# Cansat2019_1516_Payload_SectionA_v01.net
KiCad netlist of a schematic drawn in EAGLE
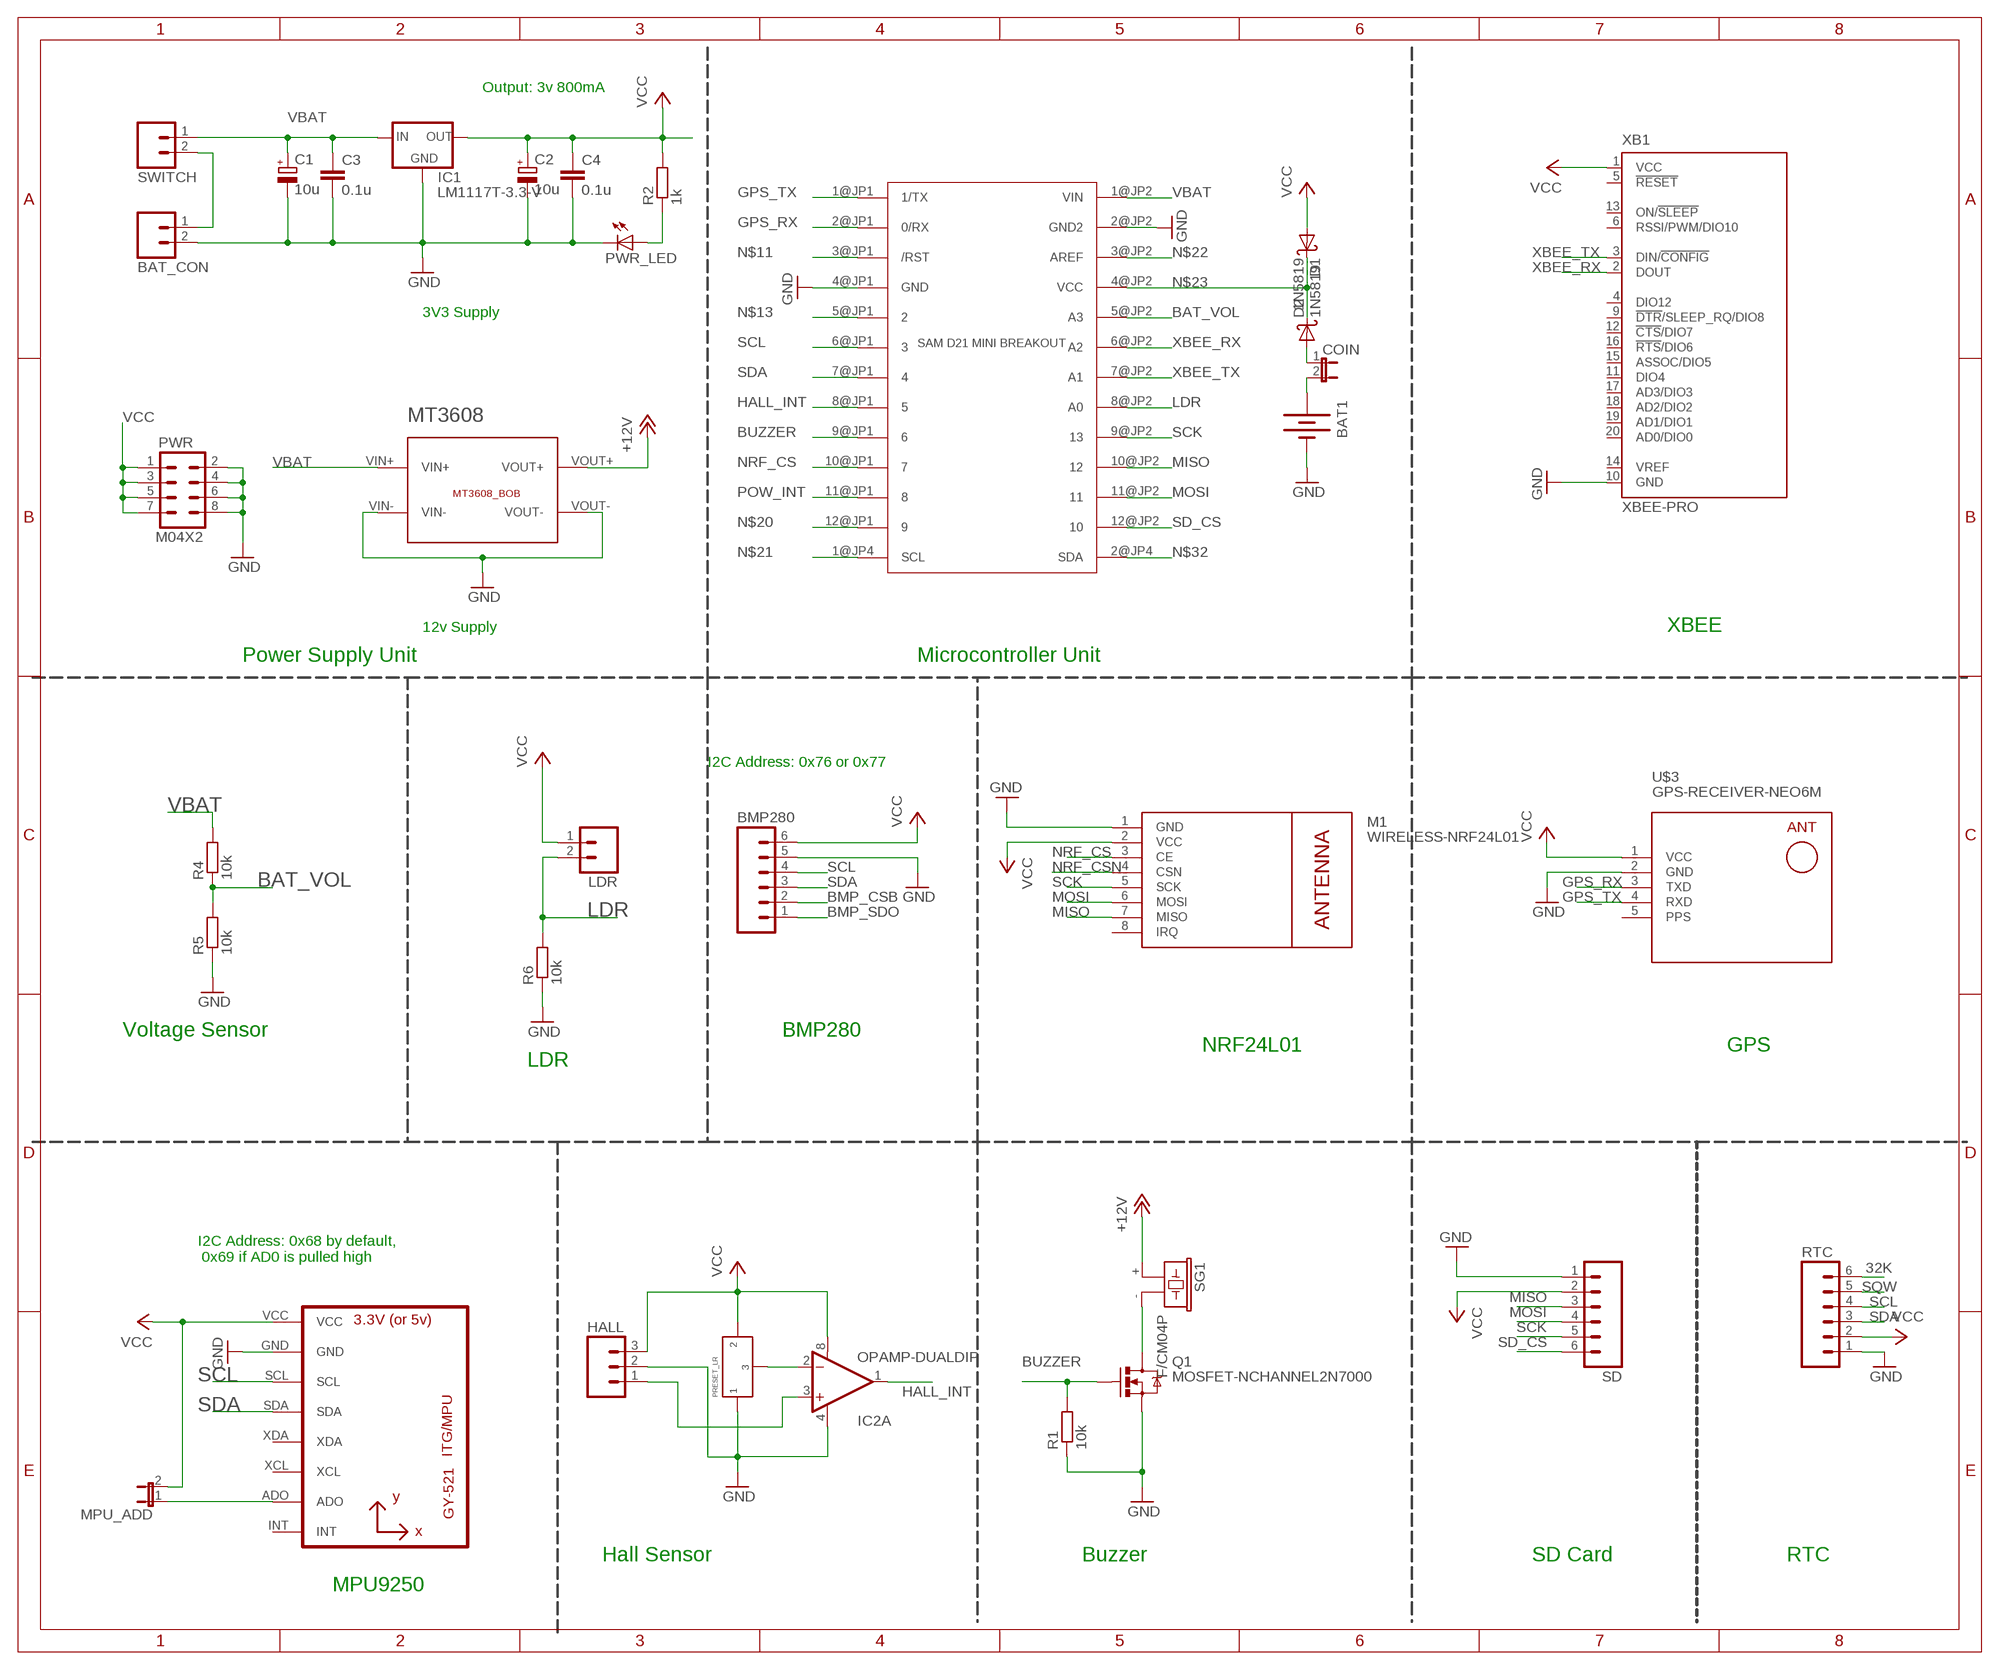
[diagram p0: schematic, sheet 1]

(export (version "E")
  (design (tool "Eeschema 10.0.6"))
  (components
    (comp (ref "BAT1")
      (value "BATTERY20PTH")
      (footprint "eagle-import:BATTCOM_20MM_PTH")
      (libsource (lib "eagle-import") (part "BATTERY20PTH"))
    )
    (comp (ref "BAT_CON")
      (value "M02")
      (footprint "eagle-import:02P")
      (libsource (lib "eagle-import") (part "M02"))
    )
    (comp (ref "BMP280")
      (value "M06")
      (footprint "eagle-import:06P")
      (libsource (lib "eagle-import") (part "M06"))
    )
    (comp (ref "C1")
      (value "10u")
      (footprint "eagle-import:E2,5-6")
      (libsource (lib "eagle-import") (part "CPOL-EUE2.5-6"))
    )
    (comp (ref "C2")
      (value "10u")
      (footprint "eagle-import:E2,5-6")
      (libsource (lib "eagle-import") (part "CPOL-EUE2.5-6"))
    )
    (comp (ref "C3")
      (value "0.1u")
      (footprint "eagle-import:C025-025X050")
      (libsource (lib "eagle-import") (part "C-EU025-025X050"))
    )
    (comp (ref "C4")
      (value "0.1u")
      (footprint "eagle-import:C025-025X050")
      (libsource (lib "eagle-import") (part "C-EU025-025X050"))
    )
    (comp (ref "COIN")
      (value "JUMPER-2PTH")
      (footprint "eagle-import:1X02")
      (libsource (lib "eagle-import") (part "JUMPER-2PTH"))
    )
    (comp (ref "D1")
      (value "1N5819")
      (footprint "eagle-import:DO41-10")
      (libsource (lib "eagle-import") (part "1N5819"))
    )
    (comp (ref "D2")
      (value "1N5819")
      (footprint "eagle-import:DO41-10")
      (libsource (lib "eagle-import") (part "1N5819"))
    )
    (comp (ref "HALL")
      (value "M03")
      (footprint "eagle-import:03P")
      (libsource (lib "eagle-import") (part "M03"))
    )
    (comp (ref "IC1")
      (value "LM1117T-3.3-V")
      (footprint "eagle-import:TO220V")
      (libsource (lib "eagle-import") (part "LM1117T--V3.3"))
    )
    (comp (ref "IC2")
      (value "OPAMP-DUALDIP")
      (footprint "eagle-import:DIP08")
      (libsource (lib "eagle-import") (part "OPAMP-DUALDIP"))
    )
    (comp (ref "LDR")
      (value "M02")
      (footprint "eagle-import:02P")
      (libsource (lib "eagle-import") (part "M02"))
    )
    (comp (ref "M1")
      (value "WIRELESS-NRF24L01")
      (footprint "eagle-import:WIRELESS-NRF24L01")
      (libsource (lib "eagle-import") (part "WIRELESS-NRF24L01"))
    )
    (comp (ref "MPU_ADD")
      (value "JUMPER-2PTH")
      (footprint "eagle-import:1X02")
      (libsource (lib "eagle-import") (part "JUMPER-2PTH"))
    )
    (comp (ref "MT3608")
      (value "MT3608_BOB")
      (footprint "eagle-import:MT3608_BOB")
      (libsource (lib "eagle-import") (part "MT3608_BOB"))
    )
    (comp (ref "PWR")
      (value "M04X2")
      (footprint "eagle-import:2X4")
      (libsource (lib "eagle-import") (part "M04X2"))
    )
    (comp (ref "PWR_LED")
      (value "LED3MM")
      (footprint "eagle-import:LED3MM")
      (libsource (lib "eagle-import") (part "LED3MM"))
    )
    (comp (ref "Q1")
      (value "MOSFET-NCHANNEL2N7000")
      (footprint "eagle-import:TO-92")
      (libsource (lib "eagle-import") (part "MOSFET-NCHANNEL2N7000"))
    )
    (comp (ref "R1")
      (value "10k")
      (footprint "eagle-import:0204_7")
      (libsource (lib "eagle-import") (part "R-EU_0204/7"))
    )
    (comp (ref "R2")
      (value "1k")
      (footprint "eagle-import:0204_7")
      (libsource (lib "eagle-import") (part "R-EU_0204/7"))
    )
    (comp (ref "R4")
      (value "10k")
      (footprint "eagle-import:0204_7")
      (libsource (lib "eagle-import") (part "R-EU_0204/7"))
    )
    (comp (ref "R5")
      (value "10k")
      (footprint "eagle-import:0204_7")
      (libsource (lib "eagle-import") (part "R-EU_0204/7"))
    )
    (comp (ref "R6")
      (value "10k")
      (footprint "eagle-import:0204_7")
      (libsource (lib "eagle-import") (part "R-EU_0204/7"))
    )
    (comp (ref "RTC")
      (value "M06")
      (footprint "eagle-import:06P")
      (libsource (lib "eagle-import") (part "M06"))
    )
    (comp (ref "SD")
      (value "M06")
      (footprint "eagle-import:06P")
      (libsource (lib "eagle-import") (part "M06"))
    )
    (comp (ref "SG1")
      (value "F/CM04P")
      (footprint "eagle-import:F_CM04P")
      (libsource (lib "eagle-import") (part "F/CM04P"))
    )
    (comp (ref "SWITCH")
      (value "M02")
      (footprint "eagle-import:02P")
      (libsource (lib "eagle-import") (part "M02"))
    )
    (comp (ref "U$1")
      (value "SAM_D21_MINI_BREAKOUT")
      (footprint "eagle-import:JP1_SPARKFUN-SAMD21-MINI-BREAKOUT-V10")
      (libsource (lib "eagle-import") (part "SAM_D21_MINI_BREAKOUT"))
    )
    (comp (ref "U$2")
      (value "PRESET_LR")
      (footprint "eagle-import:PRESET_LR")
      (libsource (lib "eagle-import") (part "PRESET_LR"))
    )
    (comp (ref "U$3")
      (value "GPS-RECEIVER-NEO6M")
      (footprint "eagle-import:GPS-RECEIVER-NEO6M")
      (libsource (lib "eagle-import") (part "GPS-RECEIVER-NEO6M"))
    )
    (comp (ref "U1")
      (value "GY-521MPU6050")
      (footprint "eagle-import:GY-521")
      (libsource (lib "eagle-import") (part "GY-521MPU6050"))
    )
    (comp (ref "XB1")
      (value "XBEE-PRO")
      (footprint "eagle-import:XBEE-PRO")
      (fields (field (name "MPN") "XBP24-AWI-001"))
      (libsource (lib "eagle-import") (part "XBEE-PRO"))
    )
  )
  (nets
    (net (code "1") (name "+12V") (class "Default")
      (node (ref "MT3608") (pin "VOUT+") (pinfunction "VOUT+_VOUT+") (pintype "bidirectional"))
      (node (ref "SG1") (pin "+") (pinfunction "1_+") (pintype "passive"))
    )
    (net (code "2") (name "/32K") (class "Default")
      (node (ref "RTC") (pin "6") (pinfunction "6_6") (pintype "passive"))
    )
    (net (code "3") (name "/BAT_VOL") (class "Default")
      (node (ref "R4") (pin "1") (pinfunction "1_1") (pintype "passive"))
      (node (ref "R5") (pin "2") (pinfunction "2_2") (pintype "passive"))
      (node (ref "U$1") (pin "5@JP2") (pinfunction "A3_5@JP2") (pintype "bidirectional"))
    )
    (net (code "4") (name "/BMP_CSB") (class "Default")
      (node (ref "BMP280") (pin "2") (pinfunction "2_2") (pintype "passive"))
    )
    (net (code "5") (name "/BMP_SDO") (class "Default")
      (node (ref "BMP280") (pin "1") (pinfunction "1_1") (pintype "passive"))
    )
    (net (code "6") (name "/BUZZER") (class "Default")
      (node (ref "Q1") (pin "2") (pinfunction "G_2") (pintype "passive"))
      (node (ref "R1") (pin "2") (pinfunction "2_2") (pintype "passive"))
      (node (ref "U$1") (pin "9@JP1") (pinfunction "6_9@JP1") (pintype "bidirectional"))
    )
    (net (code "7") (name "/GPS_RX") (class "Default")
      (node (ref "U$1") (pin "2@JP1") (pinfunction "0/RX_2@JP1") (pintype "bidirectional"))
      (node (ref "U$3") (pin "3") (pinfunction "TXD_3") (pintype "bidirectional"))
    )
    (net (code "8") (name "/GPS_TX") (class "Default")
      (node (ref "U$1") (pin "1@JP1") (pinfunction "1/TX_1@JP1") (pintype "bidirectional"))
      (node (ref "U$3") (pin "4") (pinfunction "RXD_4") (pintype "power_in"))
    )
    (net (code "9") (name "/HALL_INT") (class "Default")
      (node (ref "IC2") (pin "1") (pinfunction "OUT_1") (pintype "output"))
      (node (ref "U$1") (pin "8@JP1") (pinfunction "5_8@JP1") (pintype "bidirectional"))
    )
    (net (code "10") (name "/LDR") (class "Default")
      (node (ref "LDR") (pin "2") (pinfunction "2_2") (pintype "passive"))
      (node (ref "R6") (pin "2") (pinfunction "2_2") (pintype "passive"))
      (node (ref "U$1") (pin "8@JP2") (pinfunction "A0_8@JP2") (pintype "bidirectional"))
    )
    (net (code "11") (name "/MISO") (class "Default")
      (node (ref "M1") (pin "7") (pinfunction "MISO_7") (pintype "bidirectional"))
      (node (ref "SD") (pin "3") (pinfunction "3_3") (pintype "passive"))
      (node (ref "U$1") (pin "10@JP2") (pinfunction "12_10@JP2") (pintype "bidirectional"))
    )
    (net (code "12") (name "/MOSI") (class "Default")
      (node (ref "M1") (pin "6") (pinfunction "MOSI_6") (pintype "bidirectional"))
      (node (ref "SD") (pin "4") (pinfunction "4_4") (pintype "passive"))
      (node (ref "U$1") (pin "11@JP2") (pinfunction "11_11@JP2") (pintype "bidirectional"))
    )
    (net (code "13") (name "/N$11") (class "Default")
      (node (ref "U$1") (pin "3@JP1") (pinfunction "/RST_3@JP1") (pintype "input"))
    )
    (net (code "14") (name "/N$13") (class "Default")
      (node (ref "U$1") (pin "5@JP1") (pinfunction "2_5@JP1") (pintype "bidirectional"))
    )
    (net (code "15") (name "/N$20") (class "Default")
      (node (ref "U$1") (pin "12@JP1") (pinfunction "9_12@JP1") (pintype "bidirectional"))
    )
    (net (code "16") (name "/N$21") (class "Default")
      (node (ref "U$1") (pin "1@JP4") (pinfunction "SCL_1@JP4") (pintype "bidirectional"))
    )
    (net (code "17") (name "/N$22") (class "Default")
      (node (ref "U$1") (pin "3@JP2") (pinfunction "AREF_3@JP2") (pintype "power_in"))
    )
    (net (code "18") (name "/N$23") (class "Default")
      (node (ref "D1") (pin "C") (pinfunction "C_C") (pintype "passive"))
      (node (ref "D2") (pin "C") (pinfunction "C_C") (pintype "passive"))
      (node (ref "U$1") (pin "4@JP2") (pinfunction "VCC_4@JP2") (pintype "power_in"))
    )
    (net (code "19") (name "/N$32") (class "Default")
      (node (ref "U$1") (pin "2@JP4") (pinfunction "SDA_2@JP4") (pintype "bidirectional"))
    )
    (net (code "20") (name "/NRF_CS") (class "Default")
      (node (ref "M1") (pin "3") (pinfunction "CE_3") (pintype "bidirectional"))
      (node (ref "U$1") (pin "10@JP1") (pinfunction "7_10@JP1") (pintype "bidirectional"))
    )
    (net (code "21") (name "/NRF_CSN") (class "Default")
      (node (ref "M1") (pin "4") (pinfunction "CSN_4") (pintype "bidirectional"))
    )
    (net (code "22") (name "/POW_INT") (class "Default")
      (node (ref "U$1") (pin "11@JP1") (pinfunction "8_11@JP1") (pintype "bidirectional"))
    )
    (net (code "23") (name "/PPS") (class "Default")
      (node (ref "U$3") (pin "5") (pinfunction "PPS_5") (pintype "power_in"))
    )
    (net (code "24") (name "/SCK") (class "Default")
      (node (ref "M1") (pin "5") (pinfunction "SCK_5") (pintype "bidirectional"))
      (node (ref "SD") (pin "5") (pinfunction "5_5") (pintype "passive"))
      (node (ref "U$1") (pin "9@JP2") (pinfunction "13_9@JP2") (pintype "bidirectional"))
    )
    (net (code "25") (name "/SCL") (class "Default")
      (node (ref "BMP280") (pin "4") (pinfunction "4_4") (pintype "passive"))
      (node (ref "RTC") (pin "4") (pinfunction "4_4") (pintype "passive"))
      (node (ref "U$1") (pin "6@JP1") (pinfunction "3_6@JP1") (pintype "bidirectional"))
      (node (ref "U1") (pin "SCL") (pinfunction "SCL_SCL") (pintype "bidirectional"))
    )
    (net (code "26") (name "/SDA") (class "Default")
      (node (ref "BMP280") (pin "3") (pinfunction "3_3") (pintype "passive"))
      (node (ref "RTC") (pin "3") (pinfunction "3_3") (pintype "passive"))
      (node (ref "U$1") (pin "7@JP1") (pinfunction "4_7@JP1") (pintype "bidirectional"))
      (node (ref "U1") (pin "SDA") (pinfunction "SDA_SDA") (pintype "bidirectional"))
    )
    (net (code "27") (name "/SD_CS") (class "Default")
      (node (ref "SD") (pin "6") (pinfunction "6_6") (pintype "passive"))
      (node (ref "U$1") (pin "12@JP2") (pinfunction "10_12@JP2") (pintype "bidirectional"))
    )
    (net (code "28") (name "/SQW") (class "Default")
      (node (ref "RTC") (pin "5") (pinfunction "5_5") (pintype "passive"))
    )
    (net (code "29") (name "/VBAT") (class "Default")
      (node (ref "C1") (pin "+") (pinfunction "+_+") (pintype "passive"))
      (node (ref "C3") (pin "1") (pinfunction "1_1") (pintype "passive"))
      (node (ref "IC1") (pin "3") (pinfunction "IN_3") (pintype "input"))
      (node (ref "MT3608") (pin "VIN+") (pinfunction "VIN+_VIN+") (pintype "bidirectional"))
      (node (ref "R4") (pin "2") (pinfunction "2_2") (pintype "passive"))
      (node (ref "SWITCH") (pin "1") (pinfunction "1_1") (pintype "passive"))
      (node (ref "U$1") (pin "1@JP2") (pinfunction "VIN_1@JP2") (pintype "power_in"))
    )
    (net (code "30") (name "/XBEE_RX") (class "Default")
      (node (ref "U$1") (pin "6@JP2") (pinfunction "A2_6@JP2") (pintype "bidirectional"))
      (node (ref "XB1") (pin "2") (pinfunction "DOUT_2") (pintype "output"))
    )
    (net (code "31") (name "/XBEE_TX") (class "Default")
      (node (ref "U$1") (pin "7@JP2") (pinfunction "A1_7@JP2") (pintype "bidirectional"))
      (node (ref "XB1") (pin "3") (pinfunction "DIN/~{CONFIG}_3") (pintype "input"))
    )
    (net (code "32") (name "GND") (class "Default")
      (node (ref "BAT1") (pin "2") (pinfunction "-_2") (pintype "power_in"))
      (node (ref "BAT_CON") (pin "2") (pinfunction "2_2") (pintype "passive"))
      (node (ref "BMP280") (pin "5") (pinfunction "5_5") (pintype "passive"))
      (node (ref "C1") (pin "-") (pinfunction "-_-") (pintype "passive"))
      (node (ref "C2") (pin "-") (pinfunction "-_-") (pintype "passive"))
      (node (ref "C3") (pin "2") (pinfunction "2_2") (pintype "passive"))
      (node (ref "C4") (pin "2") (pinfunction "2_2") (pintype "passive"))
      (node (ref "HALL") (pin "2") (pinfunction "2_2") (pintype "passive"))
      (node (ref "IC1") (pin "1") (pinfunction "GND_1") (pintype "input"))
      (node (ref "IC2") (pin "4") (pinfunction "V-_4") (pintype "power_in"))
      (node (ref "M1") (pin "1") (pinfunction "GND_1") (pintype "power_in"))
      (node (ref "MT3608") (pin "VIN-") (pinfunction "VIN-_VIN-") (pintype "bidirectional"))
      (node (ref "MT3608") (pin "VOUT-") (pinfunction "VOUT-_VOUT-") (pintype "bidirectional"))
      (node (ref "PWR") (pin "2") (pinfunction "2_2") (pintype "passive"))
      (node (ref "PWR") (pin "4") (pinfunction "4_4") (pintype "passive"))
      (node (ref "PWR") (pin "6") (pinfunction "6_6") (pintype "passive"))
      (node (ref "PWR") (pin "8") (pinfunction "8_8") (pintype "passive"))
      (node (ref "PWR_LED") (pin "K") (pinfunction "C_K") (pintype "passive"))
      (node (ref "Q1") (pin "1") (pinfunction "S_1") (pintype "passive"))
      (node (ref "R1") (pin "1") (pinfunction "1_1") (pintype "passive"))
      (node (ref "R5") (pin "1") (pinfunction "1_1") (pintype "passive"))
      (node (ref "R6") (pin "1") (pinfunction "1_1") (pintype "passive"))
      (node (ref "RTC") (pin "1") (pinfunction "1_1") (pintype "passive"))
      (node (ref "SD") (pin "1") (pinfunction "1_1") (pintype "passive"))
      (node (ref "U$1") (pin "2@JP2") (pinfunction "GND2_2@JP2") (pintype "power_in"))
      (node (ref "U$1") (pin "4@JP1") (pinfunction "GND_4@JP1") (pintype "power_in"))
      (node (ref "U$2") (pin "P$1") (pinfunction "1_P$1") (pintype "passive"))
      (node (ref "U$3") (pin "2") (pinfunction "GND_2") (pintype "bidirectional"))
      (node (ref "U1") (pin "GND") (pinfunction "GND_GND") (pintype "bidirectional"))
      (node (ref "XB1") (pin "10") (pinfunction "GND_10") (pintype "power_in"))
    )
    (net (code "33") (name "Net-(BAT1-+)") (class "Default")
      (node (ref "BAT1") (pin "1") (pinfunction "+_1") (pintype "power_in"))
      (node (ref "COIN") (pin "2") (pinfunction "2_2") (pintype "passive"))
    )
    (net (code "34") (name "Net-(BAT_CON-Pad1)") (class "Default")
      (node (ref "BAT_CON") (pin "1") (pinfunction "1_1") (pintype "passive"))
      (node (ref "SWITCH") (pin "2") (pinfunction "2_2") (pintype "passive"))
    )
    (net (code "35") (name "Net-(COIN-Pad1)") (class "Default")
      (node (ref "COIN") (pin "1") (pinfunction "1_1") (pintype "passive"))
      (node (ref "D2") (pin "A") (pinfunction "A_A") (pintype "passive"))
    )
    (net (code "36") (name "Net-(IC2A-+IN)") (class "Default")
      (node (ref "HALL") (pin "1") (pinfunction "1_1") (pintype "passive"))
      (node (ref "IC2") (pin "3") (pinfunction "+IN_3") (pintype "input"))
    )
    (net (code "37") (name "Net-(IC2A--IN)") (class "Default")
      (node (ref "IC2") (pin "2") (pinfunction "-IN_2") (pintype "input"))
      (node (ref "U$2") (pin "P$3") (pinfunction "3_P$3") (pintype "passive"))
    )
    (net (code "38") (name "Net-(MPU_ADD-Pad1)") (class "Default")
      (node (ref "MPU_ADD") (pin "1") (pinfunction "1_1") (pintype "passive"))
      (node (ref "U1") (pin "ADO") (pinfunction "ADO_ADO") (pintype "bidirectional"))
    )
    (net (code "39") (name "Net-(PWR_LED-PadA)") (class "Default")
      (node (ref "PWR_LED") (pin "A") (pinfunction "A_A") (pintype "passive"))
      (node (ref "R2") (pin "1") (pinfunction "1_1") (pintype "passive"))
    )
    (net (code "40") (name "Net-(Q1-D)") (class "Default")
      (node (ref "Q1") (pin "3") (pinfunction "D_3") (pintype "passive"))
      (node (ref "SG1") (pin "-") (pinfunction "2_-") (pintype "passive"))
    )
    (net (code "41") (name "VCC") (class "Default")
      (node (ref "BMP280") (pin "6") (pinfunction "6_6") (pintype "passive"))
      (node (ref "C2") (pin "+") (pinfunction "+_+") (pintype "passive"))
      (node (ref "C4") (pin "1") (pinfunction "1_1") (pintype "passive"))
      (node (ref "D1") (pin "A") (pinfunction "A_A") (pintype "passive"))
      (node (ref "HALL") (pin "3") (pinfunction "3_3") (pintype "passive"))
      (node (ref "IC1") (pin "2") (pinfunction "OUT_2") (pintype "passive"))
      (node (ref "IC2") (pin "8") (pinfunction "V+_8") (pintype "power_in"))
      (node (ref "LDR") (pin "1") (pinfunction "1_1") (pintype "passive"))
      (node (ref "M1") (pin "2") (pinfunction "VCC_2") (pintype "power_in"))
      (node (ref "MPU_ADD") (pin "2") (pinfunction "2_2") (pintype "passive"))
      (node (ref "PWR") (pin "1") (pinfunction "1_1") (pintype "passive"))
      (node (ref "PWR") (pin "3") (pinfunction "3_3") (pintype "passive"))
      (node (ref "PWR") (pin "5") (pinfunction "5_5") (pintype "passive"))
      (node (ref "PWR") (pin "7") (pinfunction "7_7") (pintype "passive"))
      (node (ref "R2") (pin "2") (pinfunction "2_2") (pintype "passive"))
      (node (ref "RTC") (pin "2") (pinfunction "2_2") (pintype "passive"))
      (node (ref "SD") (pin "2") (pinfunction "2_2") (pintype "passive"))
      (node (ref "U$2") (pin "P$2") (pinfunction "2_P$2") (pintype "passive"))
      (node (ref "U$3") (pin "1") (pinfunction "VCC_1") (pintype "bidirectional"))
      (node (ref "U1") (pin "VCC") (pinfunction "VCC_VCC") (pintype "bidirectional"))
      (node (ref "XB1") (pin "1") (pinfunction "VCC_1") (pintype "power_in"))
    )
    (net (code "42") (name "unconnected-(M1-IRQ-Pad8)") (class "Default")
      (node (ref "M1") (pin "8") (pinfunction "IRQ_8") (pintype "bidirectional"))
    )
    (net (code "43") (name "unconnected-(U1-PadINT)") (class "Default")
      (node (ref "U1") (pin "INT") (pinfunction "INT_INT") (pintype "bidirectional"))
    )
    (net (code "44") (name "unconnected-(U1-PadXCL)") (class "Default")
      (node (ref "U1") (pin "XCL") (pinfunction "XCL_XCL") (pintype "bidirectional"))
    )
    (net (code "45") (name "unconnected-(U1-PadXDA)") (class "Default")
      (node (ref "U1") (pin "XDA") (pinfunction "XDA_XDA") (pintype "bidirectional"))
    )
    (net (code "46") (name "unconnected-(XB1-AD0{slash}DIO0-Pad20)") (class "Default")
      (node (ref "XB1") (pin "20") (pinfunction "AD0/DIO0_20") (pintype "bidirectional"))
    )
    (net (code "47") (name "unconnected-(XB1-AD1{slash}DIO1-Pad19)") (class "Default")
      (node (ref "XB1") (pin "19") (pinfunction "AD1/DIO1_19") (pintype "bidirectional"))
    )
    (net (code "48") (name "unconnected-(XB1-AD2{slash}DIO2-Pad18)") (class "Default")
      (node (ref "XB1") (pin "18") (pinfunction "AD2/DIO2_18") (pintype "bidirectional"))
    )
    (net (code "49") (name "unconnected-(XB1-AD3{slash}DIO3-Pad17)") (class "Default")
      (node (ref "XB1") (pin "17") (pinfunction "AD3/DIO3_17") (pintype "bidirectional"))
    )
    (net (code "50") (name "unconnected-(XB1-ASSOC{slash}DIO5-Pad15)") (class "Default")
      (node (ref "XB1") (pin "15") (pinfunction "ASSOC/DIO5_15") (pintype "bidirectional"))
    )
    (net (code "51") (name "unconnected-(XB1-DIO4-Pad11)") (class "Default")
      (node (ref "XB1") (pin "11") (pinfunction "DIO4_11") (pintype "bidirectional"))
    )
    (net (code "52") (name "unconnected-(XB1-DIO12-Pad4)") (class "Default")
      (node (ref "XB1") (pin "4") (pinfunction "DIO12_4") (pintype "bidirectional"))
    )
    (net (code "53") (name "unconnected-(XB1-ON{slash}~{SLEEP}-Pad13)") (class "Default")
      (node (ref "XB1") (pin "13") (pinfunction "ON/~{SLEEP}_13") (pintype "output"))
    )
    (net (code "54") (name "unconnected-(XB1-RSSI{slash}PWM{slash}DIO10-Pad6)") (class "Default")
      (node (ref "XB1") (pin "6") (pinfunction "RSSI/PWM/DIO10_6") (pintype "output"))
    )
    (net (code "55") (name "unconnected-(XB1-VREF-Pad14)") (class "Default")
      (node (ref "XB1") (pin "14") (pinfunction "VREF_14") (pintype "input"))
    )
    (net (code "56") (name "unconnected-(XB1-~{CTS}{slash}DIO7-Pad12)") (class "Default")
      (node (ref "XB1") (pin "12") (pinfunction "~{CTS}/DIO7_12") (pintype "bidirectional"))
    )
    (net (code "57") (name "unconnected-(XB1-~{DTR}{slash}SLEEP_RQ{slash}DIO8-Pad9)") (class "Default")
      (node (ref "XB1") (pin "9") (pinfunction "~{DTR}/SLEEP_RQ/DIO8_9") (pintype "bidirectional"))
    )
    (net (code "58") (name "unconnected-(XB1-~{RESET}-Pad5)") (class "Default")
      (node (ref "XB1") (pin "5") (pinfunction "~{RESET}_5") (pintype "input"))
    )
    (net (code "59") (name "unconnected-(XB1-~{RTS}{slash}DIO6-Pad16)") (class "Default")
      (node (ref "XB1") (pin "16") (pinfunction "~{RTS}/DIO6_16") (pintype "bidirectional"))
    )
  )
)
